# relay-attentuator-THRU.net
KiCad netlist of a schematic drawn in EAGLE
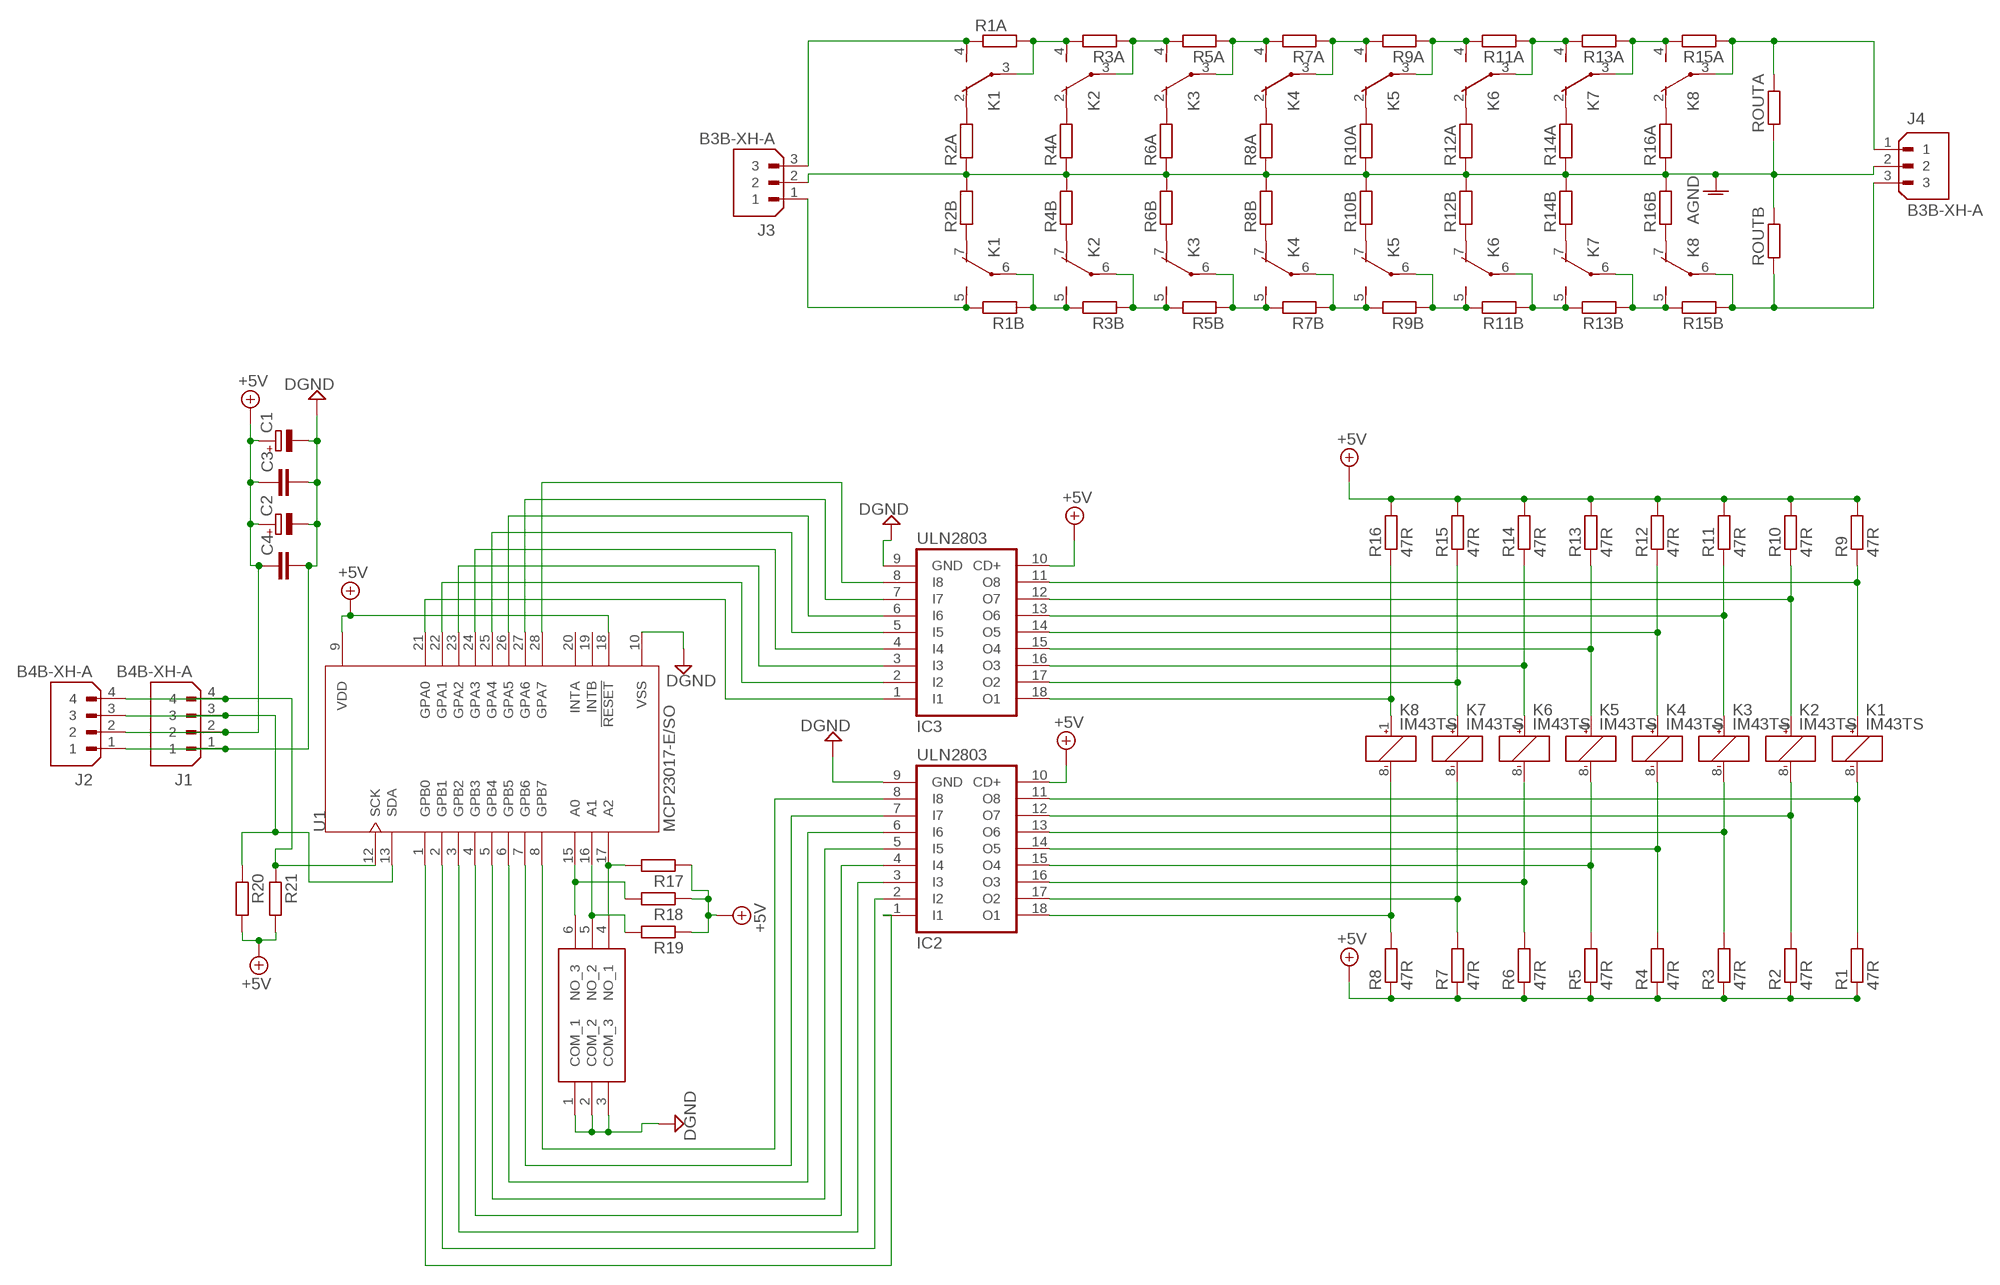
[diagram p0: schematic, sheet 1]

(export (version "E")
  (design (tool "Eeschema 10.0.6"))
  (components
    (comp (ref "C1")
      (value "CPOL-EUE3.5-8")
      (footprint "eagle-import:E3,5-8")
      (libsource (lib "eagle-import") (part "CPOL-EUE3.5-8"))
    )
    (comp (ref "C2")
      (value "CPOL-EUE3.5-8")
      (footprint "eagle-import:E3,5-8")
      (libsource (lib "eagle-import") (part "CPOL-EUE3.5-8"))
    )
    (comp (ref "C3")
      (value "C-EUC1206")
      (footprint "eagle-import:C1206")
      (libsource (lib "eagle-import") (part "C-EUC1206"))
    )
    (comp (ref "C4")
      (value "C-EUC1206")
      (footprint "eagle-import:C1206")
      (libsource (lib "eagle-import") (part "C-EUC1206"))
    )
    (comp (ref "IC2")
      (value "ULN2803")
      (footprint "eagle-import:SO-18W")
      (libsource (lib "eagle-import") (part "ULN2803ADW"))
    )
    (comp (ref "IC3")
      (value "ULN2803")
      (footprint "eagle-import:SO-18W")
      (libsource (lib "eagle-import") (part "ULN2803ADW"))
    )
    (comp (ref "J1")
      (value "B4B-XH-A")
      (footprint "eagle-import:JST_B4B-XH-A")
      (fields (field (name "MF") "JST Sales"))
      (libsource (lib "eagle-import") (part "B4B-XH-A"))
    )
    (comp (ref "J2")
      (value "B4B-XH-A")
      (footprint "eagle-import:JST_B4B-XH-A")
      (fields (field (name "MF") "JST Sales"))
      (libsource (lib "eagle-import") (part "B4B-XH-A"))
    )
    (comp (ref "J3")
      (value "B3B-XH-A")
      (footprint "eagle-import:JST_B3B-XH-A")
      (fields (field (name "MF") "JST Sales"))
      (libsource (lib "eagle-import") (part "B3B-XH-A"))
    )
    (comp (ref "J4")
      (value "B3B-XH-A")
      (footprint "eagle-import:JST_B3B-XH-A")
      (fields (field (name "MF") "JST Sales"))
      (libsource (lib "eagle-import") (part "B3B-XH-A"))
    )
    (comp (ref "K1")
      (value "IM43TS")
      (footprint "eagle-import:IM43TS")
      (libsource (lib "eagle-import") (part "IM43TS"))
    )
    (comp (ref "K2")
      (value "IM43TS")
      (footprint "eagle-import:IM43TS")
      (libsource (lib "eagle-import") (part "IM43TS"))
    )
    (comp (ref "K3")
      (value "IM43TS")
      (footprint "eagle-import:IM43TS")
      (libsource (lib "eagle-import") (part "IM43TS"))
    )
    (comp (ref "K4")
      (value "IM43TS")
      (footprint "eagle-import:IM43TS")
      (libsource (lib "eagle-import") (part "IM43TS"))
    )
    (comp (ref "K5")
      (value "IM43TS")
      (footprint "eagle-import:IM43TS")
      (libsource (lib "eagle-import") (part "IM43TS"))
    )
    (comp (ref "K6")
      (value "IM43TS")
      (footprint "eagle-import:IM43TS")
      (libsource (lib "eagle-import") (part "IM43TS"))
    )
    (comp (ref "K7")
      (value "IM43TS")
      (footprint "eagle-import:IM43TS")
      (libsource (lib "eagle-import") (part "IM43TS"))
    )
    (comp (ref "K8")
      (value "IM43TS")
      (footprint "eagle-import:IM43TS")
      (libsource (lib "eagle-import") (part "IM43TS"))
    )
    (comp (ref "R1")
      (value "47R")
      (footprint "eagle-import:R1206")
      (libsource (lib "eagle-import") (part "R-EU_R1206"))
    )
    (comp (ref "R1A")
      (value "R-EU_0207/10")
      (footprint "eagle-import:0207_10")
      (libsource (lib "eagle-import") (part "R-EU_0207/10"))
    )
    (comp (ref "R1B")
      (value "R-EU_0207/10")
      (footprint "eagle-import:0207_10")
      (libsource (lib "eagle-import") (part "R-EU_0207/10"))
    )
    (comp (ref "R2")
      (value "47R")
      (footprint "eagle-import:R1206")
      (libsource (lib "eagle-import") (part "R-EU_R1206"))
    )
    (comp (ref "R2A")
      (value "R-EU_0207/10")
      (footprint "eagle-import:0207_10")
      (libsource (lib "eagle-import") (part "R-EU_0207/10"))
    )
    (comp (ref "R2B")
      (value "R-EU_0207/10")
      (footprint "eagle-import:0207_10")
      (libsource (lib "eagle-import") (part "R-EU_0207/10"))
    )
    (comp (ref "R3")
      (value "47R")
      (footprint "eagle-import:R1206")
      (libsource (lib "eagle-import") (part "R-EU_R1206"))
    )
    (comp (ref "R3A")
      (value "R-EU_0207/10")
      (footprint "eagle-import:0207_10")
      (libsource (lib "eagle-import") (part "R-EU_0207/10"))
    )
    (comp (ref "R3B")
      (value "R-EU_0207/10")
      (footprint "eagle-import:0207_10")
      (libsource (lib "eagle-import") (part "R-EU_0207/10"))
    )
    (comp (ref "R4")
      (value "47R")
      (footprint "eagle-import:R1206")
      (libsource (lib "eagle-import") (part "R-EU_R1206"))
    )
    (comp (ref "R4A")
      (value "R-EU_0207/10")
      (footprint "eagle-import:0207_10")
      (libsource (lib "eagle-import") (part "R-EU_0207/10"))
    )
    (comp (ref "R4B")
      (value "R-EU_0207/10")
      (footprint "eagle-import:0207_10")
      (libsource (lib "eagle-import") (part "R-EU_0207/10"))
    )
    (comp (ref "R5")
      (value "47R")
      (footprint "eagle-import:R1206")
      (libsource (lib "eagle-import") (part "R-EU_R1206"))
    )
    (comp (ref "R5A")
      (value "R-EU_0207/10")
      (footprint "eagle-import:0207_10")
      (libsource (lib "eagle-import") (part "R-EU_0207/10"))
    )
    (comp (ref "R5B")
      (value "R-EU_0207/10")
      (footprint "eagle-import:0207_10")
      (libsource (lib "eagle-import") (part "R-EU_0207/10"))
    )
    (comp (ref "R6")
      (value "47R")
      (footprint "eagle-import:R1206")
      (libsource (lib "eagle-import") (part "R-EU_R1206"))
    )
    (comp (ref "R6A")
      (value "R-EU_0207/10")
      (footprint "eagle-import:0207_10")
      (libsource (lib "eagle-import") (part "R-EU_0207/10"))
    )
    (comp (ref "R6B")
      (value "R-EU_0207/10")
      (footprint "eagle-import:0207_10")
      (libsource (lib "eagle-import") (part "R-EU_0207/10"))
    )
    (comp (ref "R7")
      (value "47R")
      (footprint "eagle-import:R1206")
      (libsource (lib "eagle-import") (part "R-EU_R1206"))
    )
    (comp (ref "R7A")
      (value "R-EU_0207/10")
      (footprint "eagle-import:0207_10")
      (libsource (lib "eagle-import") (part "R-EU_0207/10"))
    )
    (comp (ref "R7B")
      (value "R-EU_0207/10")
      (footprint "eagle-import:0207_10")
      (libsource (lib "eagle-import") (part "R-EU_0207/10"))
    )
    (comp (ref "R8")
      (value "47R")
      (footprint "eagle-import:R1206")
      (libsource (lib "eagle-import") (part "R-EU_R1206"))
    )
    (comp (ref "R8A")
      (value "R-EU_0207/10")
      (footprint "eagle-import:0207_10")
      (libsource (lib "eagle-import") (part "R-EU_0207/10"))
    )
    (comp (ref "R8B")
      (value "R-EU_0207/10")
      (footprint "eagle-import:0207_10")
      (libsource (lib "eagle-import") (part "R-EU_0207/10"))
    )
    (comp (ref "R9")
      (value "47R")
      (footprint "eagle-import:R1206")
      (libsource (lib "eagle-import") (part "R-EU_R1206"))
    )
    (comp (ref "R9A")
      (value "R-EU_0207/10")
      (footprint "eagle-import:0207_10")
      (libsource (lib "eagle-import") (part "R-EU_0207/10"))
    )
    (comp (ref "R9B")
      (value "R-EU_0207/10")
      (footprint "eagle-import:0207_10")
      (libsource (lib "eagle-import") (part "R-EU_0207/10"))
    )
    (comp (ref "R10")
      (value "47R")
      (footprint "eagle-import:R1206")
      (libsource (lib "eagle-import") (part "R-EU_R1206"))
    )
    (comp (ref "R10A")
      (value "R-EU_0207/10")
      (footprint "eagle-import:0207_10")
      (libsource (lib "eagle-import") (part "R-EU_0207/10"))
    )
    (comp (ref "R10B")
      (value "R-EU_0207/10")
      (footprint "eagle-import:0207_10")
      (libsource (lib "eagle-import") (part "R-EU_0207/10"))
    )
    (comp (ref "R11")
      (value "47R")
      (footprint "eagle-import:R1206")
      (libsource (lib "eagle-import") (part "R-EU_R1206"))
    )
    (comp (ref "R11A")
      (value "R-EU_0207/10")
      (footprint "eagle-import:0207_10")
      (libsource (lib "eagle-import") (part "R-EU_0207/10"))
    )
    (comp (ref "R11B")
      (value "R-EU_0207/10")
      (footprint "eagle-import:0207_10")
      (libsource (lib "eagle-import") (part "R-EU_0207/10"))
    )
    (comp (ref "R12")
      (value "47R")
      (footprint "eagle-import:R1206")
      (libsource (lib "eagle-import") (part "R-EU_R1206"))
    )
    (comp (ref "R12A")
      (value "R-EU_0207/10")
      (footprint "eagle-import:0207_10")
      (libsource (lib "eagle-import") (part "R-EU_0207/10"))
    )
    (comp (ref "R12B")
      (value "R-EU_0207/10")
      (footprint "eagle-import:0207_10")
      (libsource (lib "eagle-import") (part "R-EU_0207/10"))
    )
    (comp (ref "R13")
      (value "47R")
      (footprint "eagle-import:R1206")
      (libsource (lib "eagle-import") (part "R-EU_R1206"))
    )
    (comp (ref "R13A")
      (value "R-EU_0207/10")
      (footprint "eagle-import:0207_10")
      (libsource (lib "eagle-import") (part "R-EU_0207/10"))
    )
    (comp (ref "R13B")
      (value "R-EU_0207/10")
      (footprint "eagle-import:0207_10")
      (libsource (lib "eagle-import") (part "R-EU_0207/10"))
    )
    (comp (ref "R14")
      (value "47R")
      (footprint "eagle-import:R1206")
      (libsource (lib "eagle-import") (part "R-EU_R1206"))
    )
    (comp (ref "R14A")
      (value "R-EU_0207/10")
      (footprint "eagle-import:0207_10")
      (libsource (lib "eagle-import") (part "R-EU_0207/10"))
    )
    (comp (ref "R14B")
      (value "R-EU_0207/10")
      (footprint "eagle-import:0207_10")
      (libsource (lib "eagle-import") (part "R-EU_0207/10"))
    )
    (comp (ref "R15")
      (value "47R")
      (footprint "eagle-import:R1206")
      (libsource (lib "eagle-import") (part "R-EU_R1206"))
    )
    (comp (ref "R15A")
      (value "R-EU_0207/10")
      (footprint "eagle-import:0207_10")
      (libsource (lib "eagle-import") (part "R-EU_0207/10"))
    )
    (comp (ref "R15B")
      (value "R-EU_0207/10")
      (footprint "eagle-import:0207_10")
      (libsource (lib "eagle-import") (part "R-EU_0207/10"))
    )
    (comp (ref "R16")
      (value "47R")
      (footprint "eagle-import:R1206")
      (libsource (lib "eagle-import") (part "R-EU_R1206"))
    )
    (comp (ref "R16A")
      (value "R-EU_0207/10")
      (footprint "eagle-import:0207_10")
      (libsource (lib "eagle-import") (part "R-EU_0207/10"))
    )
    (comp (ref "R16B")
      (value "R-EU_0207/10")
      (footprint "eagle-import:0207_10")
      (libsource (lib "eagle-import") (part "R-EU_0207/10"))
    )
    (comp (ref "R17")
      (value "47R")
      (footprint "eagle-import:R1206")
      (libsource (lib "eagle-import") (part "R-EU_R1206"))
    )
    (comp (ref "R18")
      (value "47R")
      (footprint "eagle-import:R1206")
      (libsource (lib "eagle-import") (part "R-EU_R1206"))
    )
    (comp (ref "R19")
      (value "47R")
      (footprint "eagle-import:R1206")
      (libsource (lib "eagle-import") (part "R-EU_R1206"))
    )
    (comp (ref "R20")
      (value "47R")
      (footprint "eagle-import:R1206")
      (libsource (lib "eagle-import") (part "R-EU_R1206"))
    )
    (comp (ref "R21")
      (value "47R")
      (footprint "eagle-import:R1206")
      (libsource (lib "eagle-import") (part "R-EU_R1206"))
    )
    (comp (ref "ROUTA")
      (value "R-EU_0207/10")
      (footprint "eagle-import:0207_10")
      (libsource (lib "eagle-import") (part "R-EU_0207/10"))
    )
    (comp (ref "ROUTB")
      (value "R-EU_0207/10")
      (footprint "eagle-import:0207_10")
      (libsource (lib "eagle-import") (part "R-EU_0207/10"))
    )
    (comp (ref "S1")
      (value "2454982-2")
      (footprint "eagle-import:24549822")
      (fields (field (name "MOUSER_PART_NUMBER") "655-2454982-2"))
      (libsource (lib "eagle-import") (part "2454982-2"))
    )
    (comp (ref "U1")
      (value "MCP23017-E/SO")
      (footprint "eagle-import:SOIC127P1030X265-28N")
      (fields (field (name "MF") "Microchip"))
      (libsource (lib "eagle-import") (part "MCP23017-E/SO"))
    )
  )
  (nets
    (net (code "1") (name "+5V") (class "Default")
      (node (ref "C1") (pin "+") (pinfunction "+_+") (pintype "passive"))
      (node (ref "C2") (pin "+") (pinfunction "+_+") (pintype "passive"))
      (node (ref "C3") (pin "1") (pinfunction "1_1") (pintype "passive"))
      (node (ref "C4") (pin "1") (pinfunction "1_1") (pintype "passive"))
      (node (ref "IC2") (pin "10") (pinfunction "CD+_10") (pintype "passive"))
      (node (ref "IC3") (pin "10") (pinfunction "CD+_10") (pintype "passive"))
      (node (ref "J1") (pin "2") (pinfunction "2_2") (pintype "passive"))
      (node (ref "J2") (pin "2") (pinfunction "2_2") (pintype "passive"))
      (node (ref "R1") (pin "1") (pinfunction "1_1") (pintype "passive"))
      (node (ref "R10") (pin "2") (pinfunction "2_2") (pintype "passive"))
      (node (ref "R11") (pin "2") (pinfunction "2_2") (pintype "passive"))
      (node (ref "R12") (pin "2") (pinfunction "2_2") (pintype "passive"))
      (node (ref "R13") (pin "2") (pinfunction "2_2") (pintype "passive"))
      (node (ref "R14") (pin "2") (pinfunction "2_2") (pintype "passive"))
      (node (ref "R15") (pin "2") (pinfunction "2_2") (pintype "passive"))
      (node (ref "R16") (pin "2") (pinfunction "2_2") (pintype "passive"))
      (node (ref "R17") (pin "1") (pinfunction "1_1") (pintype "passive"))
      (node (ref "R18") (pin "1") (pinfunction "1_1") (pintype "passive"))
      (node (ref "R19") (pin "1") (pinfunction "1_1") (pintype "passive"))
      (node (ref "R2") (pin "1") (pinfunction "1_1") (pintype "passive"))
      (node (ref "R20") (pin "2") (pinfunction "2_2") (pintype "passive"))
      (node (ref "R21") (pin "2") (pinfunction "2_2") (pintype "passive"))
      (node (ref "R3") (pin "1") (pinfunction "1_1") (pintype "passive"))
      (node (ref "R4") (pin "1") (pinfunction "1_1") (pintype "passive"))
      (node (ref "R5") (pin "1") (pinfunction "1_1") (pintype "passive"))
      (node (ref "R6") (pin "1") (pinfunction "1_1") (pintype "passive"))
      (node (ref "R7") (pin "1") (pinfunction "1_1") (pintype "passive"))
      (node (ref "R8") (pin "1") (pinfunction "1_1") (pintype "passive"))
      (node (ref "R9") (pin "2") (pinfunction "2_2") (pintype "passive"))
      (node (ref "U1") (pin "18") (pinfunction "~{RESET}_18") (pintype "output"))
      (node (ref "U1") (pin "9") (pinfunction "VDD_9") (pintype "power_in"))
    )
    (net (code "2") (name "AGND") (class "Default")
      (node (ref "J3") (pin "2") (pinfunction "2_2") (pintype "passive"))
      (node (ref "J4") (pin "2") (pinfunction "2_2") (pintype "passive"))
      (node (ref "R10A") (pin "1") (pinfunction "1_1") (pintype "passive"))
      (node (ref "R10B") (pin "2") (pinfunction "2_2") (pintype "passive"))
      (node (ref "R12A") (pin "1") (pinfunction "1_1") (pintype "passive"))
      (node (ref "R12B") (pin "2") (pinfunction "2_2") (pintype "passive"))
      (node (ref "R14A") (pin "1") (pinfunction "1_1") (pintype "passive"))
      (node (ref "R14B") (pin "2") (pinfunction "2_2") (pintype "passive"))
      (node (ref "R16A") (pin "1") (pinfunction "1_1") (pintype "passive"))
      (node (ref "R16B") (pin "2") (pinfunction "2_2") (pintype "passive"))
      (node (ref "R2A") (pin "1") (pinfunction "1_1") (pintype "passive"))
      (node (ref "R2B") (pin "2") (pinfunction "2_2") (pintype "passive"))
      (node (ref "R4A") (pin "1") (pinfunction "1_1") (pintype "passive"))
      (node (ref "R4B") (pin "2") (pinfunction "2_2") (pintype "passive"))
      (node (ref "R6A") (pin "1") (pinfunction "1_1") (pintype "passive"))
      (node (ref "R6B") (pin "2") (pinfunction "2_2") (pintype "passive"))
      (node (ref "R8A") (pin "1") (pinfunction "1_1") (pintype "passive"))
      (node (ref "R8B") (pin "2") (pinfunction "2_2") (pintype "passive"))
      (node (ref "ROUTA") (pin "1") (pinfunction "1_1") (pintype "passive"))
      (node (ref "ROUTB") (pin "2") (pinfunction "2_2") (pintype "passive"))
    )
    (net (code "3") (name "DGND") (class "Default")
      (node (ref "C1") (pin "-") (pinfunction "-_-") (pintype "passive"))
      (node (ref "C2") (pin "-") (pinfunction "-_-") (pintype "passive"))
      (node (ref "C3") (pin "2") (pinfunction "2_2") (pintype "passive"))
      (node (ref "C4") (pin "2") (pinfunction "2_2") (pintype "passive"))
      (node (ref "IC2") (pin "9") (pinfunction "GND_9") (pintype "power_in"))
      (node (ref "IC3") (pin "9") (pinfunction "GND_9") (pintype "power_in"))
      (node (ref "J1") (pin "1") (pinfunction "1_1") (pintype "passive"))
      (node (ref "J2") (pin "1") (pinfunction "1_1") (pintype "passive"))
      (node (ref "S1") (pin "1") (pinfunction "COM_1_1") (pintype "bidirectional"))
      (node (ref "S1") (pin "2") (pinfunction "COM_2_2") (pintype "bidirectional"))
      (node (ref "S1") (pin "3") (pinfunction "COM_3_3") (pintype "bidirectional"))
      (node (ref "U1") (pin "10") (pinfunction "VSS_10") (pintype "power_in"))
    )
    (net (code "4") (name "Net-(IC2-I1)") (class "Default")
      (node (ref "IC2") (pin "1") (pinfunction "I1_1") (pintype "input"))
      (node (ref "U1") (pin "1") (pinfunction "GPB0_1") (pintype "bidirectional"))
    )
    (net (code "5") (name "Net-(IC2-I2)") (class "Default")
      (node (ref "IC2") (pin "2") (pinfunction "I2_2") (pintype "input"))
      (node (ref "U1") (pin "2") (pinfunction "GPB1_2") (pintype "bidirectional"))
    )
    (net (code "6") (name "Net-(IC2-I3)") (class "Default")
      (node (ref "IC2") (pin "3") (pinfunction "I3_3") (pintype "input"))
      (node (ref "U1") (pin "3") (pinfunction "GPB2_3") (pintype "bidirectional"))
    )
    (net (code "7") (name "Net-(IC2-I4)") (class "Default")
      (node (ref "IC2") (pin "4") (pinfunction "I4_4") (pintype "input"))
      (node (ref "U1") (pin "4") (pinfunction "GPB3_4") (pintype "bidirectional"))
    )
    (net (code "8") (name "Net-(IC2-I5)") (class "Default")
      (node (ref "IC2") (pin "5") (pinfunction "I5_5") (pintype "input"))
      (node (ref "U1") (pin "5") (pinfunction "GPB4_5") (pintype "bidirectional"))
    )
    (net (code "9") (name "Net-(IC2-I6)") (class "Default")
      (node (ref "IC2") (pin "6") (pinfunction "I6_6") (pintype "input"))
      (node (ref "U1") (pin "6") (pinfunction "GPB5_6") (pintype "bidirectional"))
    )
    (net (code "10") (name "Net-(IC2-I7)") (class "Default")
      (node (ref "IC2") (pin "7") (pinfunction "I7_7") (pintype "input"))
      (node (ref "U1") (pin "7") (pinfunction "GPB6_7") (pintype "bidirectional"))
    )
    (net (code "11") (name "Net-(IC2-I8)") (class "Default")
      (node (ref "IC2") (pin "8") (pinfunction "I8_8") (pintype "input"))
      (node (ref "U1") (pin "8") (pinfunction "GPB7_8") (pintype "bidirectional"))
    )
    (net (code "12") (name "Net-(IC2-O1)") (class "Default")
      (node (ref "IC2") (pin "18") (pinfunction "O1_18") (pintype "open_collector"))
      (node (ref "K8") (pin "8") (pinfunction "-_8") (pintype "passive"))
      (node (ref "R8") (pin "2") (pinfunction "2_2") (pintype "passive"))
    )
    (net (code "13") (name "Net-(IC2-O2)") (class "Default")
      (node (ref "IC2") (pin "17") (pinfunction "O2_17") (pintype "open_collector"))
      (node (ref "K7") (pin "8") (pinfunction "-_8") (pintype "passive"))
      (node (ref "R7") (pin "2") (pinfunction "2_2") (pintype "passive"))
    )
    (net (code "14") (name "Net-(IC2-O3)") (class "Default")
      (node (ref "IC2") (pin "16") (pinfunction "O3_16") (pintype "open_collector"))
      (node (ref "K6") (pin "8") (pinfunction "-_8") (pintype "passive"))
      (node (ref "R6") (pin "2") (pinfunction "2_2") (pintype "passive"))
    )
    (net (code "15") (name "Net-(IC2-O4)") (class "Default")
      (node (ref "IC2") (pin "15") (pinfunction "O4_15") (pintype "open_collector"))
      (node (ref "K5") (pin "8") (pinfunction "-_8") (pintype "passive"))
      (node (ref "R5") (pin "2") (pinfunction "2_2") (pintype "passive"))
    )
    (net (code "16") (name "Net-(IC2-O5)") (class "Default")
      (node (ref "IC2") (pin "14") (pinfunction "O5_14") (pintype "open_collector"))
      (node (ref "K4") (pin "8") (pinfunction "-_8") (pintype "passive"))
      (node (ref "R4") (pin "2") (pinfunction "2_2") (pintype "passive"))
    )
    (net (code "17") (name "Net-(IC2-O6)") (class "Default")
      (node (ref "IC2") (pin "13") (pinfunction "O6_13") (pintype "open_collector"))
      (node (ref "K3") (pin "8") (pinfunction "-_8") (pintype "passive"))
      (node (ref "R3") (pin "2") (pinfunction "2_2") (pintype "passive"))
    )
    (net (code "18") (name "Net-(IC2-O7)") (class "Default")
      (node (ref "IC2") (pin "12") (pinfunction "O7_12") (pintype "open_collector"))
      (node (ref "K2") (pin "8") (pinfunction "-_8") (pintype "passive"))
      (node (ref "R2") (pin "2") (pinfunction "2_2") (pintype "passive"))
    )
    (net (code "19") (name "Net-(IC2-O8)") (class "Default")
      (node (ref "IC2") (pin "11") (pinfunction "O8_11") (pintype "open_collector"))
      (node (ref "K1") (pin "8") (pinfunction "-_8") (pintype "passive"))
      (node (ref "R1") (pin "2") (pinfunction "2_2") (pintype "passive"))
    )
    (net (code "20") (name "Net-(IC3-I1)") (class "Default")
      (node (ref "IC3") (pin "1") (pinfunction "I1_1") (pintype "input"))
      (node (ref "U1") (pin "21") (pinfunction "GPA0_21") (pintype "bidirectional"))
    )
    (net (code "21") (name "Net-(IC3-I2)") (class "Default")
      (node (ref "IC3") (pin "2") (pinfunction "I2_2") (pintype "input"))
      (node (ref "U1") (pin "22") (pinfunction "GPA1_22") (pintype "bidirectional"))
    )
    (net (code "22") (name "Net-(IC3-I3)") (class "Default")
      (node (ref "IC3") (pin "3") (pinfunction "I3_3") (pintype "input"))
      (node (ref "U1") (pin "23") (pinfunction "GPA2_23") (pintype "bidirectional"))
    )
    (net (code "23") (name "Net-(IC3-I4)") (class "Default")
      (node (ref "IC3") (pin "4") (pinfunction "I4_4") (pintype "input"))
      (node (ref "U1") (pin "24") (pinfunction "GPA3_24") (pintype "bidirectional"))
    )
    (net (code "24") (name "Net-(IC3-I5)") (class "Default")
      (node (ref "IC3") (pin "5") (pinfunction "I5_5") (pintype "input"))
      (node (ref "U1") (pin "25") (pinfunction "GPA4_25") (pintype "bidirectional"))
    )
    (net (code "25") (name "Net-(IC3-I6)") (class "Default")
      (node (ref "IC3") (pin "6") (pinfunction "I6_6") (pintype "input"))
      (node (ref "U1") (pin "26") (pinfunction "GPA5_26") (pintype "bidirectional"))
    )
    (net (code "26") (name "Net-(IC3-I7)") (class "Default")
      (node (ref "IC3") (pin "7") (pinfunction "I7_7") (pintype "input"))
      (node (ref "U1") (pin "27") (pinfunction "GPA6_27") (pintype "bidirectional"))
    )
    (net (code "27") (name "Net-(IC3-I8)") (class "Default")
      (node (ref "IC3") (pin "8") (pinfunction "I8_8") (pintype "input"))
      (node (ref "U1") (pin "28") (pinfunction "GPA7_28") (pintype "bidirectional"))
    )
    (net (code "28") (name "Net-(IC3-O1)") (class "Default")
      (node (ref "IC3") (pin "18") (pinfunction "O1_18") (pintype "open_collector"))
      (node (ref "K8") (pin "1") (pinfunction "+_1") (pintype "passive"))
      (node (ref "R16") (pin "1") (pinfunction "1_1") (pintype "passive"))
    )
    (net (code "29") (name "Net-(IC3-O2)") (class "Default")
      (node (ref "IC3") (pin "17") (pinfunction "O2_17") (pintype "open_collector"))
      (node (ref "K7") (pin "1") (pinfunction "+_1") (pintype "passive"))
      (node (ref "R15") (pin "1") (pinfunction "1_1") (pintype "passive"))
    )
    (net (code "30") (name "Net-(IC3-O3)") (class "Default")
      (node (ref "IC3") (pin "16") (pinfunction "O3_16") (pintype "open_collector"))
      (node (ref "K6") (pin "1") (pinfunction "+_1") (pintype "passive"))
      (node (ref "R14") (pin "1") (pinfunction "1_1") (pintype "passive"))
    )
    (net (code "31") (name "Net-(IC3-O4)") (class "Default")
      (node (ref "IC3") (pin "15") (pinfunction "O4_15") (pintype "open_collector"))
      (node (ref "K5") (pin "1") (pinfunction "+_1") (pintype "passive"))
      (node (ref "R13") (pin "1") (pinfunction "1_1") (pintype "passive"))
    )
    (net (code "32") (name "Net-(IC3-O5)") (class "Default")
      (node (ref "IC3") (pin "14") (pinfunction "O5_14") (pintype "open_collector"))
      (node (ref "K4") (pin "1") (pinfunction "+_1") (pintype "passive"))
      (node (ref "R12") (pin "1") (pinfunction "1_1") (pintype "passive"))
    )
    (net (code "33") (name "Net-(IC3-O6)") (class "Default")
      (node (ref "IC3") (pin "13") (pinfunction "O6_13") (pintype "open_collector"))
      (node (ref "K3") (pin "1") (pinfunction "+_1") (pintype "passive"))
      (node (ref "R11") (pin "1") (pinfunction "1_1") (pintype "passive"))
    )
    (net (code "34") (name "Net-(IC3-O7)") (class "Default")
      (node (ref "IC3") (pin "12") (pinfunction "O7_12") (pintype "open_collector"))
      (node (ref "K2") (pin "1") (pinfunction "+_1") (pintype "passive"))
      (node (ref "R10") (pin "1") (pinfunction "1_1") (pintype "passive"))
    )
    (net (code "35") (name "Net-(IC3-O8)") (class "Default")
      (node (ref "IC3") (pin "11") (pinfunction "O8_11") (pintype "open_collector"))
      (node (ref "K1") (pin "1") (pinfunction "+_1") (pintype "passive"))
      (node (ref "R9") (pin "1") (pinfunction "1_1") (pintype "passive"))
    )
    (net (code "36") (name "Net-(K1B-O)") (class "Default")
      (node (ref "K1") (pin "2") (pinfunction "O_2") (pintype "passive"))
      (node (ref "R2A") (pin "2") (pinfunction "2_2") (pintype "passive"))
    )
    (net (code "37") (name "Net-(K1B-P)") (class "Default")
      (node (ref "K1") (pin "3") (pinfunction "P_3") (pintype "passive"))
      (node (ref "K2") (pin "4") (pinfunction "S_4") (pintype "passive"))
      (node (ref "R1A") (pin "2") (pinfunction "2_2") (pintype "passive"))
      (node (ref "R3A") (pin "2") (pinfunction "2_2") (pintype "passive"))
    )
    (net (code "38") (name "Net-(K1B-S)") (class "Default")
      (node (ref "J3") (pin "3") (pinfunction "3_3") (pintype "passive"))
      (node (ref "K1") (pin "4") (pinfunction "S_4") (pintype "passive"))
      (node (ref "R1A") (pin "1") (pinfunction "1_1") (pintype "passive"))
    )
    (net (code "39") (name "Net-(K1C-O)") (class "Default")
      (node (ref "K1") (pin "7") (pinfunction "O_7") (pintype "passive"))
      (node (ref "R2B") (pin "1") (pinfunction "1_1") (pintype "passive"))
    )
    (net (code "40") (name "Net-(K1C-P)") (class "Default")
      (node (ref "K1") (pin "6") (pinfunction "P_6") (pintype "passive"))
      (node (ref "K2") (pin "5") (pinfunction "S_5") (pintype "passive"))
      (node (ref "R1B") (pin "1") (pinfunction "1_1") (pintype "passive"))
      (node (ref "R3B") (pin "2") (pinfunction "2_2") (pintype "passive"))
    )
    (net (code "41") (name "Net-(K1C-S)") (class "Default")
      (node (ref "J3") (pin "1") (pinfunction "1_1") (pintype "passive"))
      (node (ref "K1") (pin "5") (pinfunction "S_5") (pintype "passive"))
      (node (ref "R1B") (pin "2") (pinfunction "2_2") (pintype "passive"))
    )
    (net (code "42") (name "Net-(K2B-O)") (class "Default")
      (node (ref "K2") (pin "2") (pinfunction "O_2") (pintype "passive"))
      (node (ref "R4A") (pin "2") (pinfunction "2_2") (pintype "passive"))
    )
    (net (code "43") (name "Net-(K2B-P)") (class "Default")
      (node (ref "K2") (pin "3") (pinfunction "P_3") (pintype "passive"))
      (node (ref "K3") (pin "4") (pinfunction "S_4") (pintype "passive"))
      (node (ref "R3A") (pin "1") (pinfunction "1_1") (pintype "passive"))
      (node (ref "R5A") (pin "2") (pinfunction "2_2") (pintype "passive"))
    )
    (net (code "44") (name "Net-(K2C-O)") (class "Default")
      (node (ref "K2") (pin "7") (pinfunction "O_7") (pintype "passive"))
      (node (ref "R4B") (pin "1") (pinfunction "1_1") (pintype "passive"))
    )
    (net (code "45") (name "Net-(K2C-P)") (class "Default")
      (node (ref "K2") (pin "6") (pinfunction "P_6") (pintype "passive"))
      (node (ref "K3") (pin "5") (pinfunction "S_5") (pintype "passive"))
      (node (ref "R3B") (pin "1") (pinfunction "1_1") (pintype "passive"))
      (node (ref "R5B") (pin "2") (pinfunction "2_2") (pintype "passive"))
    )
    (net (code "46") (name "Net-(K3B-O)") (class "Default")
      (node (ref "K3") (pin "2") (pinfunction "O_2") (pintype "passive"))
      (node (ref "R6A") (pin "2") (pinfunction "2_2") (pintype "passive"))
    )
    (net (code "47") (name "Net-(K3B-P)") (class "Default")
      (node (ref "K3") (pin "3") (pinfunction "P_3") (pintype "passive"))
      (node (ref "K4") (pin "4") (pinfunction "S_4") (pintype "passive"))
      (node (ref "R5A") (pin "1") (pinfunction "1_1") (pintype "passive"))
      (node (ref "R7A") (pin "2") (pinfunction "2_2") (pintype "passive"))
    )
    (net (code "48") (name "Net-(K3C-O)") (class "Default")
      (node (ref "K3") (pin "7") (pinfunction "O_7") (pintype "passive"))
      (node (ref "R6B") (pin "1") (pinfunction "1_1") (pintype "passive"))
    )
    (net (code "49") (name "Net-(K3C-P)") (class "Default")
      (node (ref "K3") (pin "6") (pinfunction "P_6") (pintype "passive"))
      (node (ref "K4") (pin "5") (pinfunction "S_5") (pintype "passive"))
      (node (ref "R5B") (pin "1") (pinfunction "1_1") (pintype "passive"))
      (node (ref "R7B") (pin "2") (pinfunction "2_2") (pintype "passive"))
    )
    (net (code "50") (name "Net-(K4B-O)") (class "Default")
      (node (ref "K4") (pin "2") (pinfunction "O_2") (pintype "passive"))
      (node (ref "R8A") (pin "2") (pinfunction "2_2") (pintype "passive"))
    )
    (net (code "51") (name "Net-(K4B-P)") (class "Default")
      (node (ref "K4") (pin "3") (pinfunction "P_3") (pintype "passive"))
      (node (ref "K5") (pin "4") (pinfunction "S_4") (pintype "passive"))
      (node (ref "R7A") (pin "1") (pinfunction "1_1") (pintype "passive"))
      (node (ref "R9A") (pin "2") (pinfunction "2_2") (pintype "passive"))
    )
    (net (code "52") (name "Net-(K4C-O)") (class "Default")
      (node (ref "K4") (pin "7") (pinfunction "O_7") (pintype "passive"))
      (node (ref "R8B") (pin "1") (pinfunction "1_1") (pintype "passive"))
    )
    (net (code "53") (name "Net-(K4C-P)") (class "Default")
      (node (ref "K4") (pin "6") (pinfunction "P_6") (pintype "passive"))
      (node (ref "K5") (pin "5") (pinfunction "S_5") (pintype "passive"))
      (node (ref "R7B") (pin "1") (pinfunction "1_1") (pintype "passive"))
      (node (ref "R9B") (pin "2") (pinfunction "2_2") (pintype "passive"))
    )
    (net (code "54") (name "Net-(K5B-O)") (class "Default")
      (node (ref "K5") (pin "2") (pinfunction "O_2") (pintype "passive"))
      (node (ref "R10A") (pin "2") (pinfunction "2_2") (pintype "passive"))
    )
    (net (code "55") (name "Net-(K5B-P)") (class "Default")
      (node (ref "K5") (pin "3") (pinfunction "P_3") (pintype "passive"))
      (node (ref "K6") (pin "4") (pinfunction "S_4") (pintype "passive"))
      (node (ref "R11A") (pin "2") (pinfunction "2_2") (pintype "passive"))
      (node (ref "R9A") (pin "1") (pinfunction "1_1") (pintype "passive"))
    )
    (net (code "56") (name "Net-(K5C-O)") (class "Default")
      (node (ref "K5") (pin "7") (pinfunction "O_7") (pintype "passive"))
      (node (ref "R10B") (pin "1") (pinfunction "1_1") (pintype "passive"))
    )
    (net (code "57") (name "Net-(K5C-P)") (class "Default")
      (node (ref "K5") (pin "6") (pinfunction "P_6") (pintype "passive"))
      (node (ref "K6") (pin "5") (pinfunction "S_5") (pintype "passive"))
      (node (ref "R11B") (pin "2") (pinfunction "2_2") (pintype "passive"))
      (node (ref "R9B") (pin "1") (pinfunction "1_1") (pintype "passive"))
    )
    (net (code "58") (name "Net-(K6B-O)") (class "Default")
      (node (ref "K6") (pin "2") (pinfunction "O_2") (pintype "passive"))
      (node (ref "R12A") (pin "2") (pinfunction "2_2") (pintype "passive"))
    )
    (net (code "59") (name "Net-(K6B-P)") (class "Default")
      (node (ref "K6") (pin "3") (pinfunction "P_3") (pintype "passive"))
      (node (ref "K7") (pin "4") (pinfunction "S_4") (pintype "passive"))
      (node (ref "R11A") (pin "1") (pinfunction "1_1") (pintype "passive"))
      (node (ref "R13A") (pin "2") (pinfunction "2_2") (pintype "passive"))
    )
    (net (code "60") (name "Net-(K6C-O)") (class "Default")
      (node (ref "K6") (pin "7") (pinfunction "O_7") (pintype "passive"))
      (node (ref "R12B") (pin "1") (pinfunction "1_1") (pintype "passive"))
    )
    (net (code "61") (name "Net-(K6C-P)") (class "Default")
      (node (ref "K6") (pin "6") (pinfunction "P_6") (pintype "passive"))
      (node (ref "K7") (pin "5") (pinfunction "S_5") (pintype "passive"))
      (node (ref "R11B") (pin "1") (pinfunction "1_1") (pintype "passive"))
      (node (ref "R13B") (pin "2") (pinfunction "2_2") (pintype "passive"))
    )
    (net (code "62") (name "Net-(K7B-O)") (class "Default")
      (node (ref "K7") (pin "2") (pinfunction "O_2") (pintype "passive"))
      (node (ref "R14A") (pin "2") (pinfunction "2_2") (pintype "passive"))
    )
    (net (code "63") (name "Net-(K7B-P)") (class "Default")
      (node (ref "K7") (pin "3") (pinfunction "P_3") (pintype "passive"))
      (node (ref "K8") (pin "4") (pinfunction "S_4") (pintype "passive"))
      (node (ref "R13A") (pin "1") (pinfunction "1_1") (pintype "passive"))
      (node (ref "R15A") (pin "2") (pinfunction "2_2") (pintype "passive"))
    )
    (net (code "64") (name "Net-(K7C-O)") (class "Default")
      (node (ref "K7") (pin "7") (pinfunction "O_7") (pintype "passive"))
      (node (ref "R14B") (pin "1") (pinfunction "1_1") (pintype "passive"))
    )
    (net (code "65") (name "Net-(K7C-P)") (class "Default")
      (node (ref "K7") (pin "6") (pinfunction "P_6") (pintype "passive"))
      (node (ref "K8") (pin "5") (pinfunction "S_5") (pintype "passive"))
      (node (ref "R13B") (pin "1") (pinfunction "1_1") (pintype "passive"))
      (node (ref "R15B") (pin "2") (pinfunction "2_2") (pintype "passive"))
    )
    (net (code "66") (name "Net-(K8B-O)") (class "Default")
      (node (ref "K8") (pin "2") (pinfunction "O_2") (pintype "passive"))
      (node (ref "R16A") (pin "2") (pinfunction "2_2") (pintype "passive"))
    )
    (net (code "67") (name "Net-(K8B-P)") (class "Default")
      (node (ref "J4") (pin "1") (pinfunction "1_1") (pintype "passive"))
      (node (ref "K8") (pin "3") (pinfunction "P_3") (pintype "passive"))
      (node (ref "R15A") (pin "1") (pinfunction "1_1") (pintype "passive"))
      (node (ref "ROUTA") (pin "2") (pinfunction "2_2") (pintype "passive"))
    )
    (net (code "68") (name "Net-(K8C-O)") (class "Default")
      (node (ref "K8") (pin "7") (pinfunction "O_7") (pintype "passive"))
      (node (ref "R16B") (pin "1") (pinfunction "1_1") (pintype "passive"))
    )
    (net (code "69") (name "Net-(K8C-P)") (class "Default")
      (node (ref "J4") (pin "3") (pinfunction "3_3") (pintype "passive"))
      (node (ref "K8") (pin "6") (pinfunction "P_6") (pintype "passive"))
      (node (ref "R15B") (pin "1") (pinfunction "1_1") (pintype "passive"))
      (node (ref "ROUTB") (pin "1") (pinfunction "1_1") (pintype "passive"))
    )
    (net (code "70") (name "Net-(S1-NO_1)") (class "Default")
      (node (ref "R17") (pin "2") (pinfunction "2_2") (pintype "passive"))
      (node (ref "S1") (pin "4") (pinfunction "NO_1_4") (pintype "bidirectional"))
      (node (ref "U1") (pin "17") (pinfunction "A2_17") (pintype "input"))
    )
    (net (code "71") (name "Net-(S1-NO_2)") (class "Default")
      (node (ref "R19") (pin "2") (pinfunction "2_2") (pintype "passive"))
      (node (ref "S1") (pin "5") (pinfunction "NO_2_5") (pintype "bidirectional"))
      (node (ref "U1") (pin "16") (pinfunction "A1_16") (pintype "input"))
    )
    (net (code "72") (name "Net-(S1-NO_3)") (class "Default")
      (node (ref "R18") (pin "2") (pinfunction "2_2") (pintype "passive"))
      (node (ref "S1") (pin "6") (pinfunction "NO_3_6") (pintype "bidirectional"))
      (node (ref "U1") (pin "15") (pinfunction "A0_15") (pintype "input"))
    )
    (net (code "73") (name "Net-(U1-SCK)") (class "Default")
      (node (ref "J1") (pin "4") (pinfunction "4_4") (pintype "passive"))
      (node (ref "J2") (pin "4") (pinfunction "4_4") (pintype "passive"))
      (node (ref "R21") (pin "1") (pinfunction "1_1") (pintype "passive"))
      (node (ref "U1") (pin "12") (pinfunction "SCK_12") (pintype "input"))
    )
    (net (code "74") (name "Net-(U1-SDA)") (class "Default")
      (node (ref "J1") (pin "3") (pinfunction "3_3") (pintype "passive"))
      (node (ref "J2") (pin "3") (pinfunction "3_3") (pintype "passive"))
      (node (ref "R20") (pin "1") (pinfunction "1_1") (pintype "passive"))
      (node (ref "U1") (pin "13") (pinfunction "SDA_13") (pintype "bidirectional"))
    )
    (net (code "75") (name "unconnected-(U1-INTA-Pad20)") (class "Default")
      (node (ref "U1") (pin "20") (pinfunction "INTA_20") (pintype "output"))
    )
    (net (code "76") (name "unconnected-(U1-INTB-Pad19)") (class "Default")
      (node (ref "U1") (pin "19") (pinfunction "INTB_19") (pintype "output"))
    )
  )
)
